# weather-cube_main_board.net
KiCad netlist of a schematic drawn in EAGLE
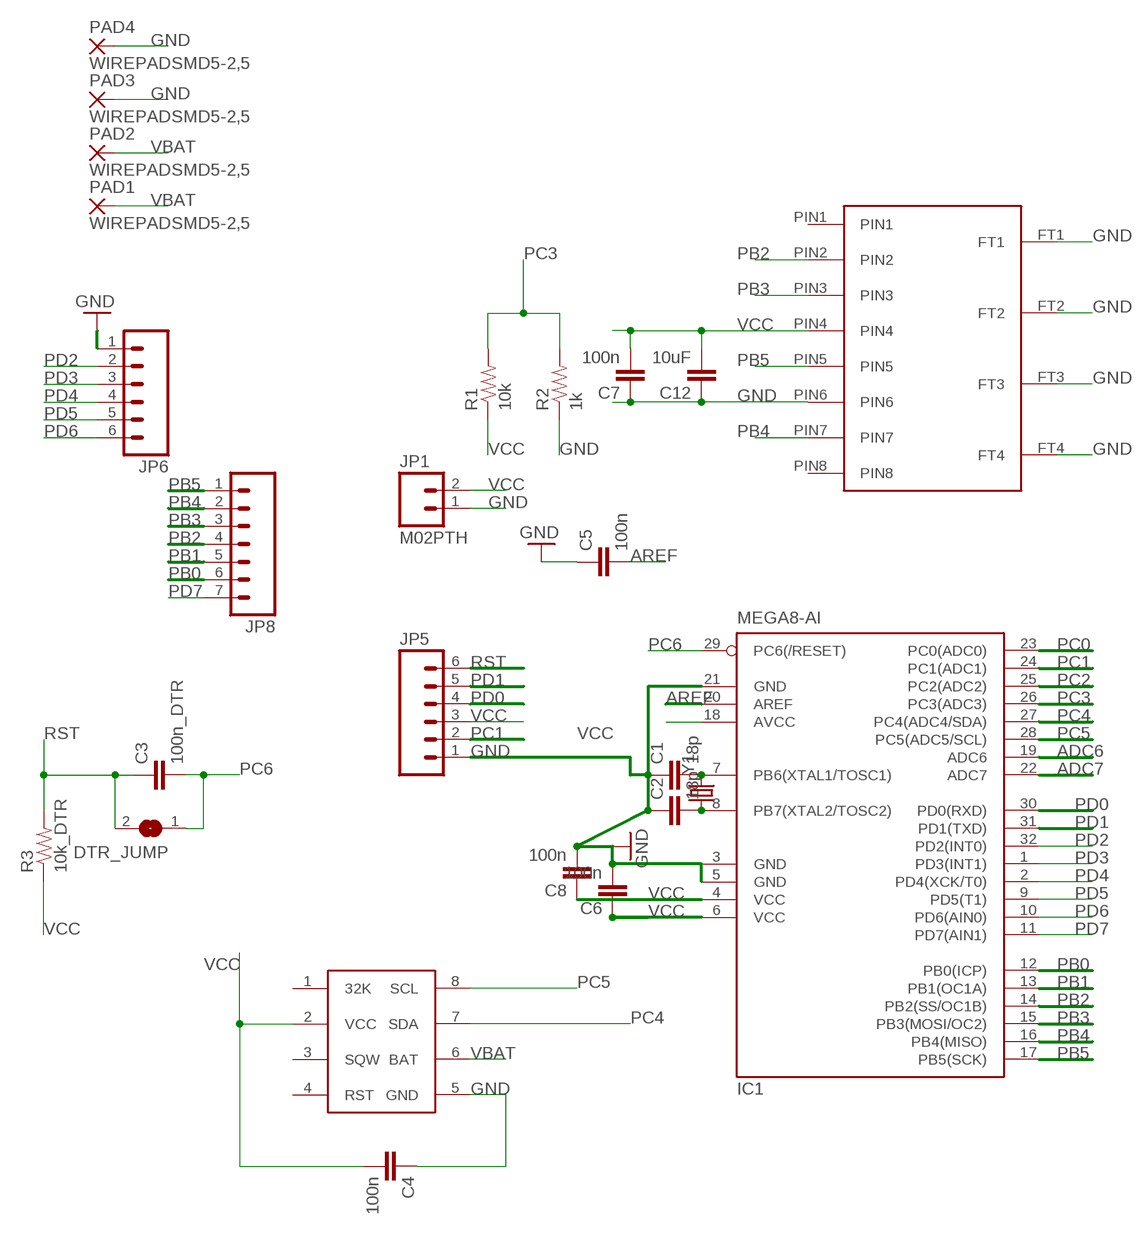
[diagram p0: schematic, sheet 1]

(export (version "E")
  (design (tool "Eeschema 10.0.6"))
  (components
    (comp (ref "*RTC")
      (value "DS3231M")
      (footprint "eagle-import:DS3231M")
      (libsource (lib "eagle-import") (part "DS3231M"))
    )
    (comp (ref "C1")
      (value "18p")
      (footprint "eagle-import:0603-CAP")
      (libsource (lib "eagle-import") (part "CAP0603-CAP"))
    )
    (comp (ref "C2")
      (value "18p")
      (footprint "eagle-import:0603-CAP")
      (libsource (lib "eagle-import") (part "CAP0603-CAP"))
    )
    (comp (ref "C3")
      (value "100n_DTR")
      (footprint "eagle-import:0603-CAP")
      (libsource (lib "eagle-import") (part "CAP0603-CAP"))
    )
    (comp (ref "C4")
      (value "100n")
      (footprint "eagle-import:0603-CAP")
      (libsource (lib "eagle-import") (part "CAP0603-CAP"))
    )
    (comp (ref "C5")
      (value "100n")
      (footprint "eagle-import:0603-CAP")
      (libsource (lib "eagle-import") (part "CAP0603-CAP"))
    )
    (comp (ref "C6")
      (value "100n")
      (footprint "eagle-import:0603-CAP")
      (libsource (lib "eagle-import") (part "CAP0603-CAP"))
    )
    (comp (ref "C7")
      (value "100n")
      (footprint "eagle-import:0603-CAP")
      (libsource (lib "eagle-import") (part "CAP0603-CAP"))
    )
    (comp (ref "C8")
      (value "100n")
      (footprint "eagle-import:0603-CAP")
      (libsource (lib "eagle-import") (part "CAP0603-CAP"))
    )
    (comp (ref "C12")
      (value "10uF")
      (footprint "eagle-import:0603-CAP")
      (libsource (lib "eagle-import") (part "CAP0603-CAP"))
    )
    (comp (ref "DTR_JUMP")
      (value "SJ")
      (footprint "eagle-import:SJ")
      (libsource (lib "eagle-import") (part "SJ"))
    )
    (comp (ref "IC1")
      (value "MEGA8-AI")
      (footprint "eagle-import:TQFP32-08")
      (fields (field (name "MPN") "ATMEGA8-16AU"))
      (libsource (lib "eagle-import") (part "MEGA8-AI"))
    )
    (comp (ref "JP1")
      (value "M02PTH")
      (footprint "eagle-import:1X02")
      (libsource (lib "eagle-import") (part "M02PTH"))
    )
    (comp (ref "JP5")
      (value "M06SIP")
      (footprint "eagle-import:1X06")
      (libsource (lib "eagle-import") (part "M06SIP"))
    )
    (comp (ref "JP6")
      (value "M06SIP")
      (footprint "eagle-import:1X06")
      (libsource (lib "eagle-import") (part "M06SIP"))
    )
    (comp (ref "JP8")
      (value "M07")
      (footprint "eagle-import:1X07")
      (libsource (lib "eagle-import") (part "M07"))
    )
    (comp (ref "MICRO-SD")
      (value "MICROSD-1010030368")
      (footprint "eagle-import:MICROSD-1010030368")
      (libsource (lib "eagle-import") (part "MICROSD-1010030368"))
    )
    (comp (ref "PAD1")
      (value "WIREPADSMD5-2,5")
      (footprint "eagle-import:5-2,5")
      (libsource (lib "eagle-import") (part "WIREPADSMD5-2,5"))
    )
    (comp (ref "PAD2")
      (value "WIREPADSMD5-2,5")
      (footprint "eagle-import:5-2,5")
      (libsource (lib "eagle-import") (part "WIREPADSMD5-2,5"))
    )
    (comp (ref "PAD3")
      (value "WIREPADSMD5-2,5")
      (footprint "eagle-import:5-2,5")
      (libsource (lib "eagle-import") (part "WIREPADSMD5-2,5"))
    )
    (comp (ref "PAD4")
      (value "WIREPADSMD5-2,5")
      (footprint "eagle-import:5-2,5")
      (libsource (lib "eagle-import") (part "WIREPADSMD5-2,5"))
    )
    (comp (ref "R1")
      (value "10k")
      (footprint "eagle-import:0603-RES")
      (libsource (lib "eagle-import") (part "RESISTOR0603"))
    )
    (comp (ref "R2")
      (value "1k")
      (footprint "eagle-import:0603-RES")
      (libsource (lib "eagle-import") (part "RESISTOR0603"))
    )
    (comp (ref "R3")
      (value "10k_DTR")
      (footprint "eagle-import:0603-RES")
      (libsource (lib "eagle-import") (part "RESISTOR0603"))
    )
    (comp (ref "Y1")
      (value "CRYSTAL5X3")
      (footprint "eagle-import:CRYSTAL-SMD-5X3")
      (libsource (lib "eagle-import") (part "CRYSTAL5X3"))
    )
  )
  (nets
    (net (code "1") (name "/ADC6") (class "Default")
      (node (ref "IC1") (pin "19") (pinfunction "ADC6_19") (pintype "bidirectional"))
    )
    (net (code "2") (name "/ADC7") (class "Default")
      (node (ref "IC1") (pin "22") (pinfunction "ADC7_22") (pintype "bidirectional"))
    )
    (net (code "3") (name "/AREF") (class "Default")
      (node (ref "C5") (pin "2") (pinfunction "2_2") (pintype "passive"))
      (node (ref "IC1") (pin "20") (pinfunction "AREF_20") (pintype "passive"))
    )
    (net (code "4") (name "/PB0") (class "Default")
      (node (ref "IC1") (pin "12") (pinfunction "PB0(ICP)_12") (pintype "bidirectional"))
      (node (ref "JP8") (pin "6") (pinfunction "6_6") (pintype "passive"))
    )
    (net (code "5") (name "/PB1") (class "Default")
      (node (ref "IC1") (pin "13") (pinfunction "PB1(OC1A)_13") (pintype "bidirectional"))
      (node (ref "JP8") (pin "5") (pinfunction "5_5") (pintype "passive"))
    )
    (net (code "6") (name "/PB2") (class "Default")
      (node (ref "IC1") (pin "14") (pinfunction "PB2(SS/OC1B)_14") (pintype "bidirectional"))
      (node (ref "JP8") (pin "4") (pinfunction "4_4") (pintype "passive"))
      (node (ref "MICRO-SD") (pin "PIN2") (pinfunction "PIN2_PIN2") (pintype "bidirectional"))
    )
    (net (code "7") (name "/PB3") (class "Default")
      (node (ref "IC1") (pin "15") (pinfunction "PB3(MOSI/OC2)_15") (pintype "bidirectional"))
      (node (ref "JP8") (pin "3") (pinfunction "3_3") (pintype "passive"))
      (node (ref "MICRO-SD") (pin "PIN3") (pinfunction "PIN3_PIN3") (pintype "bidirectional"))
    )
    (net (code "8") (name "/PB4") (class "Default")
      (node (ref "IC1") (pin "16") (pinfunction "PB4(MISO)_16") (pintype "bidirectional"))
      (node (ref "JP8") (pin "2") (pinfunction "2_2") (pintype "passive"))
      (node (ref "MICRO-SD") (pin "PIN7") (pinfunction "PIN7_PIN7") (pintype "bidirectional"))
    )
    (net (code "9") (name "/PB5") (class "Default")
      (node (ref "IC1") (pin "17") (pinfunction "PB5(SCK)_17") (pintype "bidirectional"))
      (node (ref "JP8") (pin "1") (pinfunction "1_1") (pintype "passive"))
      (node (ref "MICRO-SD") (pin "PIN5") (pinfunction "PIN5_PIN5") (pintype "bidirectional"))
    )
    (net (code "10") (name "/PC0") (class "Default")
      (node (ref "IC1") (pin "23") (pinfunction "PC0(ADC0)_23") (pintype "bidirectional"))
    )
    (net (code "11") (name "/PC1") (class "Default")
      (node (ref "IC1") (pin "24") (pinfunction "PC1(ADC1)_24") (pintype "bidirectional"))
      (node (ref "JP5") (pin "2") (pinfunction "2_2") (pintype "passive"))
    )
    (net (code "12") (name "/PC2") (class "Default")
      (node (ref "IC1") (pin "25") (pinfunction "PC2(ADC2)_25") (pintype "bidirectional"))
    )
    (net (code "13") (name "/PC3") (class "Default")
      (node (ref "IC1") (pin "26") (pinfunction "PC3(ADC3)_26") (pintype "bidirectional"))
      (node (ref "R1") (pin "2") (pinfunction "2_2") (pintype "passive"))
      (node (ref "R2") (pin "2") (pinfunction "2_2") (pintype "passive"))
    )
    (net (code "14") (name "/PC4") (class "Default")
      (node (ref "*RTC") (pin "7") (pinfunction "SDA_7") (pintype "bidirectional"))
      (node (ref "IC1") (pin "27") (pinfunction "PC4(ADC4/SDA)_27") (pintype "bidirectional"))
    )
    (net (code "15") (name "/PC5") (class "Default")
      (node (ref "*RTC") (pin "8") (pinfunction "SCL_8") (pintype "bidirectional"))
      (node (ref "IC1") (pin "28") (pinfunction "PC5(ADC5/SCL)_28") (pintype "bidirectional"))
    )
    (net (code "16") (name "/PC6") (class "Default")
      (node (ref "C3") (pin "2") (pinfunction "2_2") (pintype "passive"))
      (node (ref "DTR_JUMP") (pin "1") (pinfunction "1_1") (pintype "passive"))
      (node (ref "IC1") (pin "29") (pinfunction "PC6(/RESET)_29") (pintype "bidirectional"))
    )
    (net (code "17") (name "/PD0") (class "Default")
      (node (ref "IC1") (pin "30") (pinfunction "PD0(RXD)_30") (pintype "bidirectional"))
      (node (ref "JP5") (pin "4") (pinfunction "4_4") (pintype "passive"))
    )
    (net (code "18") (name "/PD1") (class "Default")
      (node (ref "IC1") (pin "31") (pinfunction "PD1(TXD)_31") (pintype "bidirectional"))
      (node (ref "JP5") (pin "5") (pinfunction "5_5") (pintype "passive"))
    )
    (net (code "19") (name "/PD2") (class "Default")
      (node (ref "IC1") (pin "32") (pinfunction "PD2(INT0)_32") (pintype "bidirectional"))
      (node (ref "JP6") (pin "2") (pinfunction "2_2") (pintype "passive"))
    )
    (net (code "20") (name "/PD3") (class "Default")
      (node (ref "IC1") (pin "1") (pinfunction "PD3(INT1)_1") (pintype "bidirectional"))
      (node (ref "JP6") (pin "3") (pinfunction "3_3") (pintype "passive"))
    )
    (net (code "21") (name "/PD4") (class "Default")
      (node (ref "IC1") (pin "2") (pinfunction "PD4(XCK/T0)_2") (pintype "bidirectional"))
      (node (ref "JP6") (pin "4") (pinfunction "4_4") (pintype "passive"))
    )
    (net (code "22") (name "/PD5") (class "Default")
      (node (ref "IC1") (pin "9") (pinfunction "PD5(T1)_9") (pintype "bidirectional"))
      (node (ref "JP6") (pin "5") (pinfunction "5_5") (pintype "passive"))
    )
    (net (code "23") (name "/PD6") (class "Default")
      (node (ref "IC1") (pin "10") (pinfunction "PD6(AIN0)_10") (pintype "bidirectional"))
      (node (ref "JP6") (pin "6") (pinfunction "6_6") (pintype "passive"))
    )
    (net (code "24") (name "/PD7") (class "Default")
      (node (ref "IC1") (pin "11") (pinfunction "PD7(AIN1)_11") (pintype "bidirectional"))
      (node (ref "JP8") (pin "7") (pinfunction "7_7") (pintype "passive"))
    )
    (net (code "25") (name "/RST") (class "Default")
      (node (ref "C3") (pin "1") (pinfunction "1_1") (pintype "passive"))
      (node (ref "DTR_JUMP") (pin "2") (pinfunction "2_2") (pintype "passive"))
      (node (ref "JP5") (pin "6") (pinfunction "6_6") (pintype "passive"))
      (node (ref "R3") (pin "2") (pinfunction "2_2") (pintype "passive"))
    )
    (net (code "26") (name "/VBAT") (class "Default")
      (node (ref "*RTC") (pin "6") (pinfunction "BAT_6") (pintype "bidirectional"))
      (node (ref "PAD1") (pin "1") (pinfunction "P_1") (pintype "passive"))
      (node (ref "PAD2") (pin "1") (pinfunction "P_1") (pintype "passive"))
    )
    (net (code "27") (name "/VCC") (class "Default")
      (node (ref "*RTC") (pin "2") (pinfunction "VCC_2") (pintype "bidirectional"))
      (node (ref "C12") (pin "2") (pinfunction "2_2") (pintype "passive"))
      (node (ref "C4") (pin "2") (pinfunction "2_2") (pintype "passive"))
      (node (ref "C6") (pin "1") (pinfunction "1_1") (pintype "passive"))
      (node (ref "C7") (pin "2") (pinfunction "2_2") (pintype "passive"))
      (node (ref "C8") (pin "1") (pinfunction "1_1") (pintype "passive"))
      (node (ref "IC1") (pin "18") (pinfunction "AVCC_18") (pintype "power_in"))
      (node (ref "IC1") (pin "4") (pinfunction "VCC_4") (pintype "power_in"))
      (node (ref "IC1") (pin "6") (pinfunction "VCC_6") (pintype "power_in"))
      (node (ref "JP1") (pin "2") (pinfunction "2_2") (pintype "passive"))
      (node (ref "JP5") (pin "3") (pinfunction "3_3") (pintype "passive"))
      (node (ref "MICRO-SD") (pin "PIN4") (pinfunction "PIN4_PIN4") (pintype "bidirectional"))
      (node (ref "R1") (pin "1") (pinfunction "1_1") (pintype "passive"))
      (node (ref "R3") (pin "1") (pinfunction "1_1") (pintype "passive"))
    )
    (net (code "28") (name "GND") (class "Default")
      (node (ref "*RTC") (pin "5") (pinfunction "GND_5") (pintype "bidirectional"))
      (node (ref "C1") (pin "1") (pinfunction "1_1") (pintype "passive"))
      (node (ref "C12") (pin "1") (pinfunction "1_1") (pintype "passive"))
      (node (ref "C2") (pin "1") (pinfunction "1_1") (pintype "passive"))
      (node (ref "C4") (pin "1") (pinfunction "1_1") (pintype "passive"))
      (node (ref "C5") (pin "1") (pinfunction "1_1") (pintype "passive"))
      (node (ref "C6") (pin "2") (pinfunction "2_2") (pintype "passive"))
      (node (ref "C7") (pin "1") (pinfunction "1_1") (pintype "passive"))
      (node (ref "C8") (pin "2") (pinfunction "2_2") (pintype "passive"))
      (node (ref "IC1") (pin "21") (pinfunction "GND_21") (pintype "power_in"))
      (node (ref "IC1") (pin "3") (pinfunction "GND_3") (pintype "power_in"))
      (node (ref "IC1") (pin "5") (pinfunction "GND_5") (pintype "power_in"))
      (node (ref "JP1") (pin "1") (pinfunction "1_1") (pintype "passive"))
      (node (ref "JP5") (pin "1") (pinfunction "1_1") (pintype "passive"))
      (node (ref "JP6") (pin "1") (pinfunction "1_1") (pintype "passive"))
      (node (ref "MICRO-SD") (pin "FT1") (pinfunction "FT1_FT1") (pintype "bidirectional"))
      (node (ref "MICRO-SD") (pin "FT2") (pinfunction "FT2_FT2") (pintype "bidirectional"))
      (node (ref "MICRO-SD") (pin "FT3") (pinfunction "FT3_FT3") (pintype "bidirectional"))
      (node (ref "MICRO-SD") (pin "FT4") (pinfunction "FT4_FT4") (pintype "bidirectional"))
      (node (ref "MICRO-SD") (pin "PIN6") (pinfunction "PIN6_PIN6") (pintype "bidirectional"))
      (node (ref "PAD3") (pin "1") (pinfunction "P_1") (pintype "passive"))
      (node (ref "PAD4") (pin "1") (pinfunction "P_1") (pintype "passive"))
      (node (ref "R2") (pin "1") (pinfunction "1_1") (pintype "passive"))
    )
    (net (code "29") (name "Net-(IC1-PB6(XTAL1{slash}TOSC1))") (class "Default")
      (node (ref "C1") (pin "2") (pinfunction "2_2") (pintype "passive"))
      (node (ref "IC1") (pin "7") (pinfunction "PB6(XTAL1/TOSC1)_7") (pintype "bidirectional"))
      (node (ref "Y1") (pin "3") (pinfunction "2_3") (pintype "passive"))
    )
    (net (code "30") (name "Net-(IC1-PB7(XTAL2{slash}TOSC2))") (class "Default")
      (node (ref "C2") (pin "2") (pinfunction "2_2") (pintype "passive"))
      (node (ref "IC1") (pin "8") (pinfunction "PB7(XTAL2/TOSC2)_8") (pintype "bidirectional"))
      (node (ref "Y1") (pin "1") (pinfunction "1_1") (pintype "passive"))
    )
    (net (code "31") (name "unconnected-(*RTC-32K-Pad1)") (class "Default")
      (node (ref "*RTC") (pin "1") (pinfunction "32K_1") (pintype "bidirectional"))
    )
    (net (code "32") (name "unconnected-(*RTC-RST-Pad4)") (class "Default")
      (node (ref "*RTC") (pin "4") (pinfunction "RST_4") (pintype "bidirectional"))
    )
    (net (code "33") (name "unconnected-(*RTC-SQW-Pad3)") (class "Default")
      (node (ref "*RTC") (pin "3") (pinfunction "SQW_3") (pintype "bidirectional"))
    )
    (net (code "34") (name "unconnected-(MICRO-SD-PadPIN1)") (class "Default")
      (node (ref "MICRO-SD") (pin "PIN1") (pinfunction "PIN1_PIN1") (pintype "bidirectional"))
    )
    (net (code "35") (name "unconnected-(MICRO-SD-PadPIN8)") (class "Default")
      (node (ref "MICRO-SD") (pin "PIN8") (pinfunction "PIN8_PIN8") (pintype "bidirectional"))
    )
  )
)
